# 2_unextended_ANSI_matrix.net
KiCad netlist of a schematic drawn in Altium Designer
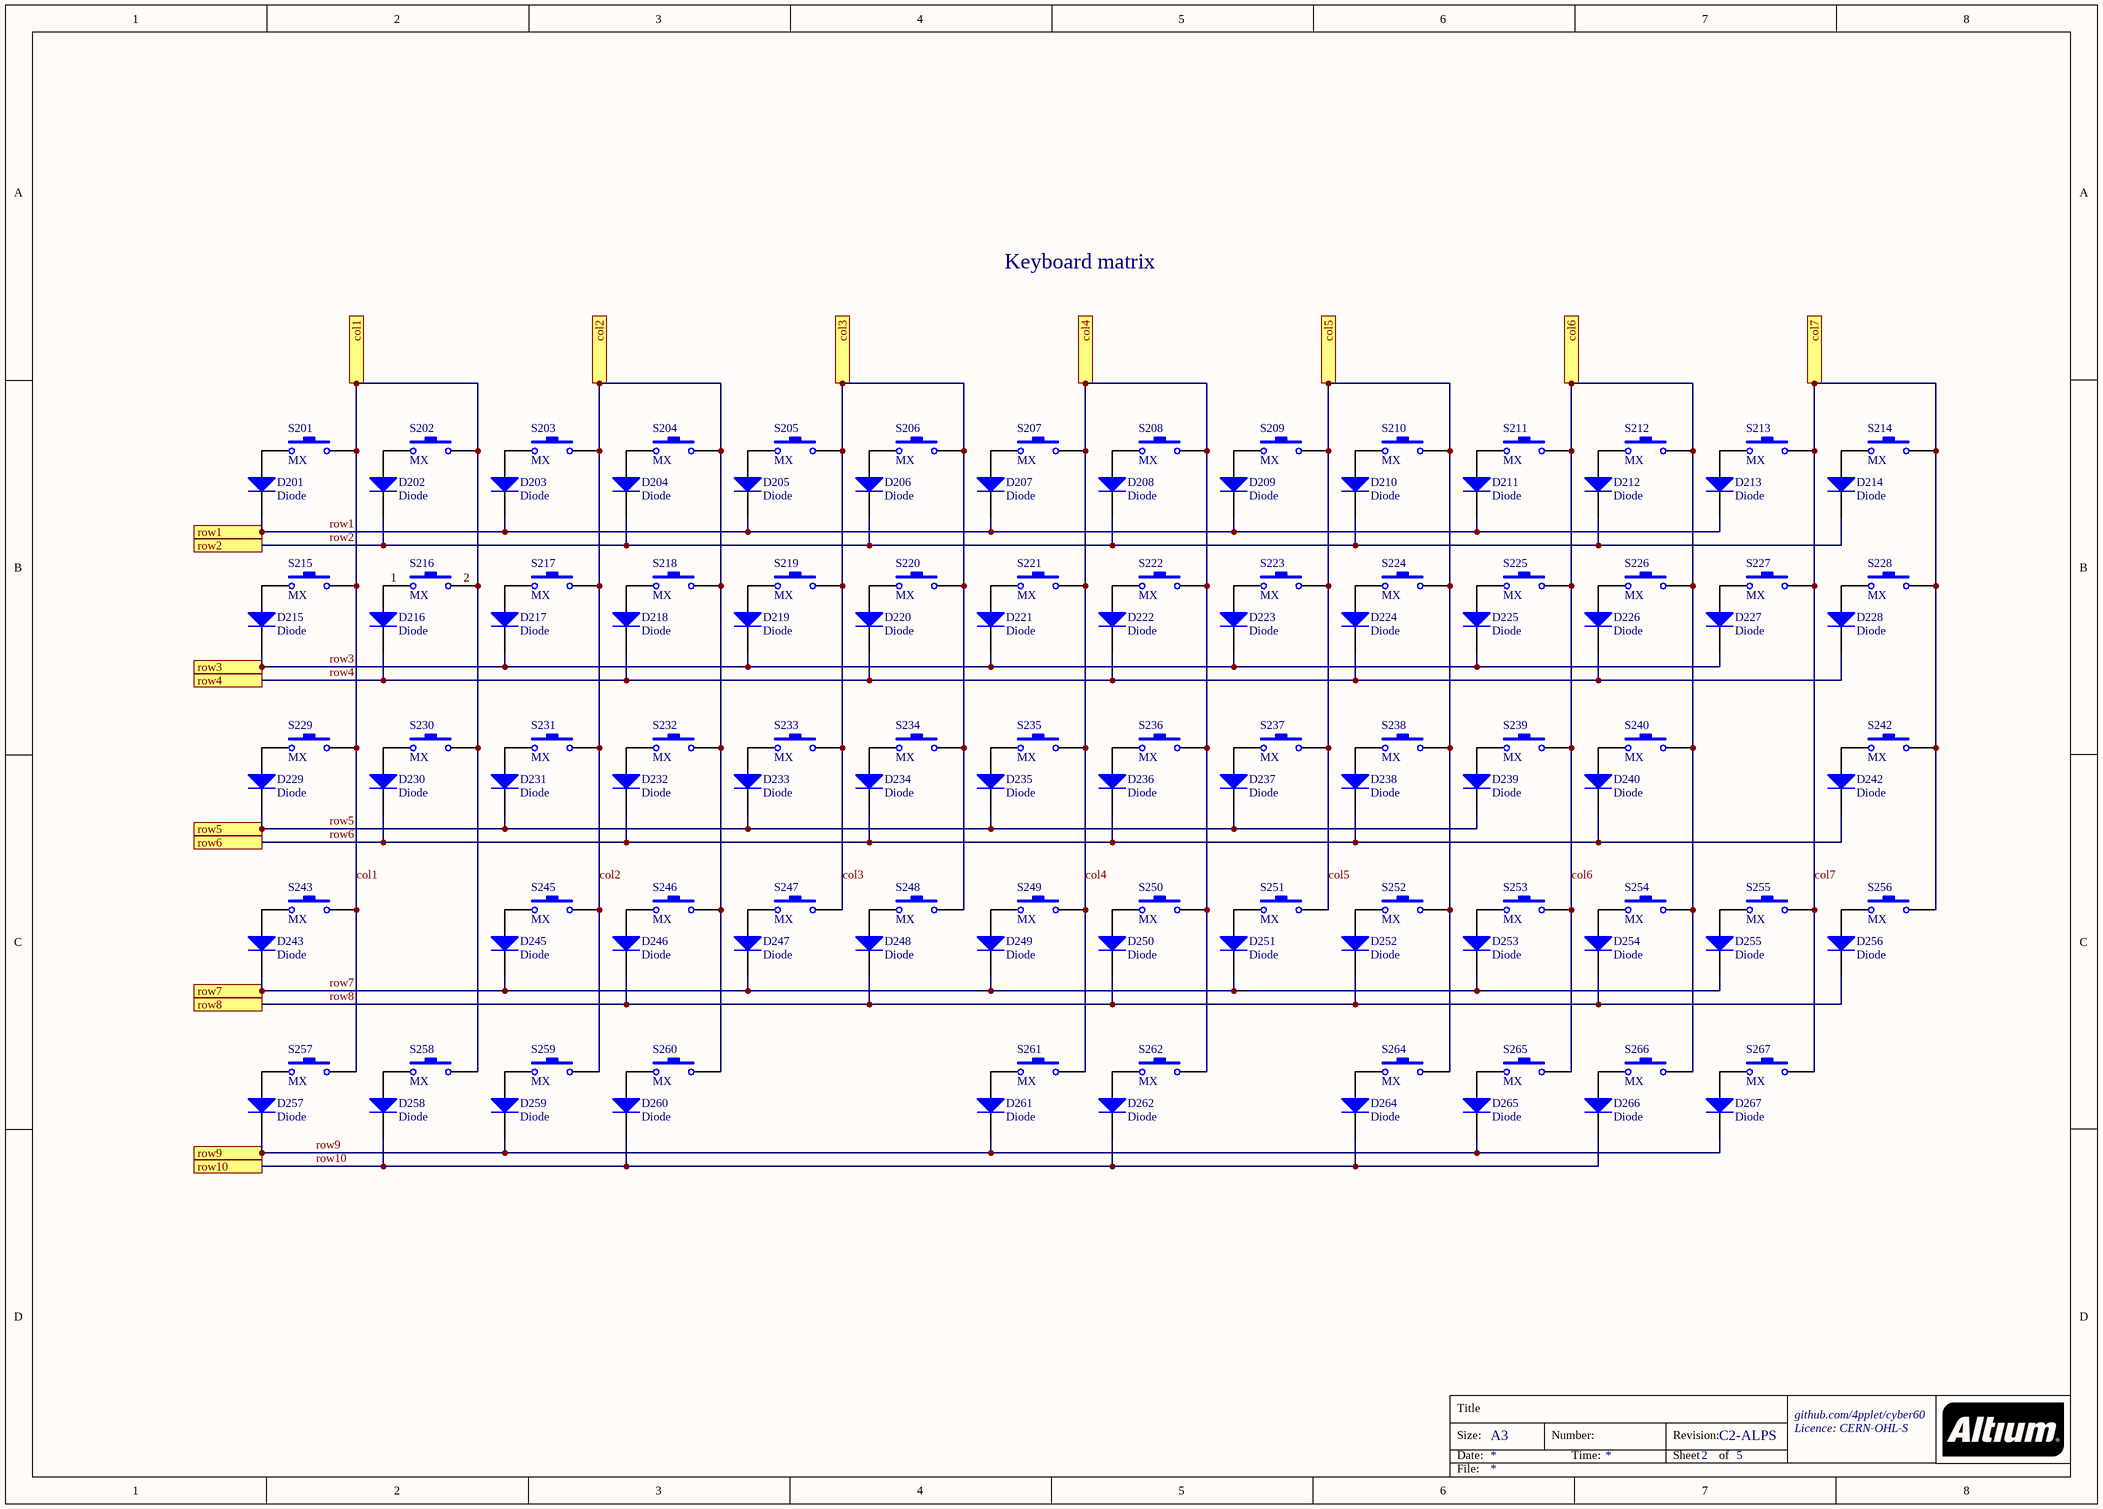
[diagram p0: 2_unextended_ANSI_matrix.SchDoc]

(export (version "E")
  (design (tool "Eeschema 10.0.6"))
  (components
    (comp (ref "D201")
      (value "Diode")
      (footprint "SOD-123")
      (description "Default Diode")
      (fields (field (name "LCSC PART #") "C81598") (field (name "MRF.PART") "1N4148W"))
      (libsource (lib "Miscellaneous Devices") (part "Diode"))
    )
    (comp (ref "D202")
      (value "Diode")
      (footprint "SOD-123")
      (description "Default Diode")
      (fields (field (name "LCSC PART #") "C81598") (field (name "MRF.PART") "1N4148W"))
      (libsource (lib "Miscellaneous Devices") (part "Diode"))
    )
    (comp (ref "D203")
      (value "Diode")
      (footprint "SOD-123")
      (description "Default Diode")
      (fields (field (name "LCSC PART #") "C81598") (field (name "MRF.PART") "1N4148W"))
      (libsource (lib "Miscellaneous Devices") (part "Diode"))
    )
    (comp (ref "D204")
      (value "Diode")
      (footprint "SOD-123")
      (description "Default Diode")
      (fields (field (name "LCSC PART #") "C81598") (field (name "MRF.PART") "1N4148W"))
      (libsource (lib "Miscellaneous Devices") (part "Diode"))
    )
    (comp (ref "D205")
      (value "Diode")
      (footprint "SOD-123")
      (description "Default Diode")
      (fields (field (name "LCSC PART #") "C81598") (field (name "MRF.PART") "1N4148W"))
      (libsource (lib "Miscellaneous Devices") (part "Diode"))
    )
    (comp (ref "D206")
      (value "Diode")
      (footprint "SOD-123")
      (description "Default Diode")
      (fields (field (name "LCSC PART #") "C81598") (field (name "MRF.PART") "1N4148W"))
      (libsource (lib "Miscellaneous Devices") (part "Diode"))
    )
    (comp (ref "D207")
      (value "Diode")
      (footprint "SOD-123")
      (description "Default Diode")
      (fields (field (name "LCSC PART #") "C81598") (field (name "MRF.PART") "1N4148W"))
      (libsource (lib "Miscellaneous Devices") (part "Diode"))
    )
    (comp (ref "D208")
      (value "Diode")
      (footprint "SOD-123")
      (description "Default Diode")
      (fields (field (name "LCSC PART #") "C81598") (field (name "MRF.PART") "1N4148W"))
      (libsource (lib "Miscellaneous Devices") (part "Diode"))
    )
    (comp (ref "D209")
      (value "Diode")
      (footprint "SOD-123")
      (description "Default Diode")
      (fields (field (name "LCSC PART #") "C81598") (field (name "MRF.PART") "1N4148W"))
      (libsource (lib "Miscellaneous Devices") (part "Diode"))
    )
    (comp (ref "D210")
      (value "Diode")
      (footprint "SOD-123")
      (description "Default Diode")
      (fields (field (name "LCSC PART #") "C81598") (field (name "MRF.PART") "1N4148W"))
      (libsource (lib "Miscellaneous Devices") (part "Diode"))
    )
    (comp (ref "D211")
      (value "Diode")
      (footprint "SOD-123")
      (description "Default Diode")
      (fields (field (name "LCSC PART #") "C81598") (field (name "MRF.PART") "1N4148W"))
      (libsource (lib "Miscellaneous Devices") (part "Diode"))
    )
    (comp (ref "D212")
      (value "Diode")
      (footprint "SOD-123")
      (description "Default Diode")
      (fields (field (name "LCSC PART #") "C81598") (field (name "MRF.PART") "1N4148W"))
      (libsource (lib "Miscellaneous Devices") (part "Diode"))
    )
    (comp (ref "D213")
      (value "Diode")
      (footprint "SOD-123")
      (description "Default Diode")
      (fields (field (name "LCSC PART #") "C81598") (field (name "MRF.PART") "1N4148W"))
      (libsource (lib "Miscellaneous Devices") (part "Diode"))
    )
    (comp (ref "D214")
      (value "Diode")
      (footprint "SOD-123")
      (description "Default Diode")
      (fields (field (name "LCSC PART #") "C81598") (field (name "MRF.PART") "1N4148W"))
      (libsource (lib "Miscellaneous Devices") (part "Diode"))
    )
    (comp (ref "D215")
      (value "Diode")
      (footprint "SOD-123")
      (description "Default Diode")
      (fields (field (name "LCSC PART #") "C81598") (field (name "MRF.PART") "1N4148W"))
      (libsource (lib "Miscellaneous Devices") (part "Diode"))
    )
    (comp (ref "D216")
      (value "Diode")
      (footprint "SOD-123")
      (description "Default Diode")
      (fields (field (name "LCSC PART #") "C81598") (field (name "MRF.PART") "1N4148W"))
      (libsource (lib "Miscellaneous Devices") (part "Diode"))
    )
    (comp (ref "D217")
      (value "Diode")
      (footprint "SOD-123")
      (description "Default Diode")
      (fields (field (name "LCSC PART #") "C81598") (field (name "MRF.PART") "1N4148W"))
      (libsource (lib "Miscellaneous Devices") (part "Diode"))
    )
    (comp (ref "D218")
      (value "Diode")
      (footprint "SOD-123")
      (description "Default Diode")
      (fields (field (name "LCSC PART #") "C81598") (field (name "MRF.PART") "1N4148W"))
      (libsource (lib "Miscellaneous Devices") (part "Diode"))
    )
    (comp (ref "D219")
      (value "Diode")
      (footprint "SOD-123")
      (description "Default Diode")
      (fields (field (name "LCSC PART #") "C81598") (field (name "MRF.PART") "1N4148W"))
      (libsource (lib "Miscellaneous Devices") (part "Diode"))
    )
    (comp (ref "D220")
      (value "Diode")
      (footprint "SOD-123")
      (description "Default Diode")
      (fields (field (name "LCSC PART #") "C81598") (field (name "MRF.PART") "1N4148W"))
      (libsource (lib "Miscellaneous Devices") (part "Diode"))
    )
    (comp (ref "D221")
      (value "Diode")
      (footprint "SOD-123")
      (description "Default Diode")
      (fields (field (name "LCSC PART #") "C81598") (field (name "MRF.PART") "1N4148W"))
      (libsource (lib "Miscellaneous Devices") (part "Diode"))
    )
    (comp (ref "D222")
      (value "Diode")
      (footprint "SOD-123")
      (description "Default Diode")
      (fields (field (name "LCSC PART #") "C81598") (field (name "MRF.PART") "1N4148W"))
      (libsource (lib "Miscellaneous Devices") (part "Diode"))
    )
    (comp (ref "D223")
      (value "Diode")
      (footprint "SOD-123")
      (description "Default Diode")
      (fields (field (name "LCSC PART #") "C81598") (field (name "MRF.PART") "1N4148W"))
      (libsource (lib "Miscellaneous Devices") (part "Diode"))
    )
    (comp (ref "D224")
      (value "Diode")
      (footprint "SOD-123")
      (description "Default Diode")
      (fields (field (name "LCSC PART #") "C81598") (field (name "MRF.PART") "1N4148W"))
      (libsource (lib "Miscellaneous Devices") (part "Diode"))
    )
    (comp (ref "D225")
      (value "Diode")
      (footprint "SOD-123")
      (description "Default Diode")
      (fields (field (name "LCSC PART #") "C81598") (field (name "MRF.PART") "1N4148W"))
      (libsource (lib "Miscellaneous Devices") (part "Diode"))
    )
    (comp (ref "D226")
      (value "Diode")
      (footprint "SOD-123")
      (description "Default Diode")
      (fields (field (name "LCSC PART #") "C81598") (field (name "MRF.PART") "1N4148W"))
      (libsource (lib "Miscellaneous Devices") (part "Diode"))
    )
    (comp (ref "D227")
      (value "Diode")
      (footprint "SOD-123")
      (description "Default Diode")
      (fields (field (name "LCSC PART #") "C81598") (field (name "MRF.PART") "1N4148W"))
      (libsource (lib "Miscellaneous Devices") (part "Diode"))
    )
    (comp (ref "D228")
      (value "Diode")
      (footprint "SOD-123")
      (description "Default Diode")
      (fields (field (name "LCSC PART #") "C81598") (field (name "MRF.PART") "1N4148W"))
      (libsource (lib "Miscellaneous Devices") (part "Diode"))
    )
    (comp (ref "D229")
      (value "Diode")
      (footprint "SOD-123")
      (description "Default Diode")
      (fields (field (name "LCSC PART #") "C81598") (field (name "MRF.PART") "1N4148W"))
      (libsource (lib "Miscellaneous Devices") (part "Diode"))
    )
    (comp (ref "D230")
      (value "Diode")
      (footprint "SOD-123")
      (description "Default Diode")
      (fields (field (name "LCSC PART #") "C81598") (field (name "MRF.PART") "1N4148W"))
      (libsource (lib "Miscellaneous Devices") (part "Diode"))
    )
    (comp (ref "D231")
      (value "Diode")
      (footprint "SOD-123")
      (description "Default Diode")
      (fields (field (name "LCSC PART #") "C81598") (field (name "MRF.PART") "1N4148W"))
      (libsource (lib "Miscellaneous Devices") (part "Diode"))
    )
    (comp (ref "D232")
      (value "Diode")
      (footprint "SOD-123")
      (description "Default Diode")
      (fields (field (name "LCSC PART #") "C81598") (field (name "MRF.PART") "1N4148W"))
      (libsource (lib "Miscellaneous Devices") (part "Diode"))
    )
    (comp (ref "D233")
      (value "Diode")
      (footprint "SOD-123")
      (description "Default Diode")
      (fields (field (name "LCSC PART #") "C81598") (field (name "MRF.PART") "1N4148W"))
      (libsource (lib "Miscellaneous Devices") (part "Diode"))
    )
    (comp (ref "D234")
      (value "Diode")
      (footprint "SOD-123")
      (description "Default Diode")
      (fields (field (name "LCSC PART #") "C81598") (field (name "MRF.PART") "1N4148W"))
      (libsource (lib "Miscellaneous Devices") (part "Diode"))
    )
    (comp (ref "D235")
      (value "Diode")
      (footprint "SOD-123")
      (description "Default Diode")
      (fields (field (name "LCSC PART #") "C81598") (field (name "MRF.PART") "1N4148W"))
      (libsource (lib "Miscellaneous Devices") (part "Diode"))
    )
    (comp (ref "D236")
      (value "Diode")
      (footprint "SOD-123")
      (description "Default Diode")
      (fields (field (name "LCSC PART #") "C81598") (field (name "MRF.PART") "1N4148W"))
      (libsource (lib "Miscellaneous Devices") (part "Diode"))
    )
    (comp (ref "D237")
      (value "Diode")
      (footprint "SOD-123")
      (description "Default Diode")
      (fields (field (name "LCSC PART #") "C81598") (field (name "MRF.PART") "1N4148W"))
      (libsource (lib "Miscellaneous Devices") (part "Diode"))
    )
    (comp (ref "D238")
      (value "Diode")
      (footprint "SOD-123")
      (description "Default Diode")
      (fields (field (name "LCSC PART #") "C81598") (field (name "MRF.PART") "1N4148W"))
      (libsource (lib "Miscellaneous Devices") (part "Diode"))
    )
    (comp (ref "D239")
      (value "Diode")
      (footprint "SOD-123")
      (description "Default Diode")
      (fields (field (name "LCSC PART #") "C81598") (field (name "MRF.PART") "1N4148W"))
      (libsource (lib "Miscellaneous Devices") (part "Diode"))
    )
    (comp (ref "D240")
      (value "Diode")
      (footprint "SOD-123")
      (description "Default Diode")
      (fields (field (name "LCSC PART #") "C81598") (field (name "MRF.PART") "1N4148W"))
      (libsource (lib "Miscellaneous Devices") (part "Diode"))
    )
    (comp (ref "D242")
      (value "Diode")
      (footprint "SOD-123")
      (description "Default Diode")
      (fields (field (name "LCSC PART #") "C81598") (field (name "MRF.PART") "1N4148W"))
      (libsource (lib "Miscellaneous Devices") (part "Diode"))
    )
    (comp (ref "D243")
      (value "Diode")
      (footprint "SOD-123")
      (description "Default Diode")
      (fields (field (name "LCSC PART #") "C81598") (field (name "MRF.PART") "1N4148W"))
      (libsource (lib "Miscellaneous Devices") (part "Diode"))
    )
    (comp (ref "D245")
      (value "Diode")
      (footprint "SOD-123")
      (description "Default Diode")
      (fields (field (name "LCSC PART #") "C81598") (field (name "MRF.PART") "1N4148W"))
      (libsource (lib "Miscellaneous Devices") (part "Diode"))
    )
    (comp (ref "D246")
      (value "Diode")
      (footprint "SOD-123")
      (description "Default Diode")
      (fields (field (name "LCSC PART #") "C81598") (field (name "MRF.PART") "1N4148W"))
      (libsource (lib "Miscellaneous Devices") (part "Diode"))
    )
    (comp (ref "D247")
      (value "Diode")
      (footprint "SOD-123")
      (description "Default Diode")
      (fields (field (name "LCSC PART #") "C81598") (field (name "MRF.PART") "1N4148W"))
      (libsource (lib "Miscellaneous Devices") (part "Diode"))
    )
    (comp (ref "D248")
      (value "Diode")
      (footprint "SOD-123")
      (description "Default Diode")
      (fields (field (name "LCSC PART #") "C81598") (field (name "MRF.PART") "1N4148W"))
      (libsource (lib "Miscellaneous Devices") (part "Diode"))
    )
    (comp (ref "D249")
      (value "Diode")
      (footprint "SOD-123")
      (description "Default Diode")
      (fields (field (name "LCSC PART #") "C81598") (field (name "MRF.PART") "1N4148W"))
      (libsource (lib "Miscellaneous Devices") (part "Diode"))
    )
    (comp (ref "D250")
      (value "Diode")
      (footprint "SOD-123")
      (description "Default Diode")
      (fields (field (name "LCSC PART #") "C81598") (field (name "MRF.PART") "1N4148W"))
      (libsource (lib "Miscellaneous Devices") (part "Diode"))
    )
    (comp (ref "D251")
      (value "Diode")
      (footprint "SOD-123")
      (description "Default Diode")
      (fields (field (name "LCSC PART #") "C81598") (field (name "MRF.PART") "1N4148W"))
      (libsource (lib "Miscellaneous Devices") (part "Diode"))
    )
    (comp (ref "D252")
      (value "Diode")
      (footprint "SOD-123")
      (description "Default Diode")
      (fields (field (name "LCSC PART #") "C81598") (field (name "MRF.PART") "1N4148W"))
      (libsource (lib "Miscellaneous Devices") (part "Diode"))
    )
    (comp (ref "D253")
      (value "Diode")
      (footprint "SOD-123")
      (description "Default Diode")
      (fields (field (name "LCSC PART #") "C81598") (field (name "MRF.PART") "1N4148W"))
      (libsource (lib "Miscellaneous Devices") (part "Diode"))
    )
    (comp (ref "D254")
      (value "Diode")
      (footprint "SOD-123")
      (description "Default Diode")
      (fields (field (name "LCSC PART #") "C81598") (field (name "MRF.PART") "1N4148W"))
      (libsource (lib "Miscellaneous Devices") (part "Diode"))
    )
    (comp (ref "D255")
      (value "Diode")
      (footprint "SOD-123")
      (description "Default Diode")
      (fields (field (name "LCSC PART #") "C81598") (field (name "MRF.PART") "1N4148W"))
      (libsource (lib "Miscellaneous Devices") (part "Diode"))
    )
    (comp (ref "D256")
      (value "Diode")
      (footprint "SOD-123")
      (description "Default Diode")
      (fields (field (name "LCSC PART #") "C81598") (field (name "MRF.PART") "1N4148W"))
      (libsource (lib "Miscellaneous Devices") (part "Diode"))
    )
    (comp (ref "D257")
      (value "Diode")
      (footprint "SOD-123")
      (description "Default Diode")
      (fields (field (name "LCSC PART #") "C81598") (field (name "MRF.PART") "1N4148W"))
      (libsource (lib "Miscellaneous Devices") (part "Diode"))
    )
    (comp (ref "D258")
      (value "Diode")
      (footprint "SOD-123")
      (description "Default Diode")
      (fields (field (name "LCSC PART #") "C81598") (field (name "MRF.PART") "1N4148W"))
      (libsource (lib "Miscellaneous Devices") (part "Diode"))
    )
    (comp (ref "D259")
      (value "Diode")
      (footprint "SOD-123")
      (description "Default Diode")
      (fields (field (name "LCSC PART #") "C81598") (field (name "MRF.PART") "1N4148W"))
      (libsource (lib "Miscellaneous Devices") (part "Diode"))
    )
    (comp (ref "D260")
      (value "Diode")
      (footprint "SOD-123")
      (description "Default Diode")
      (fields (field (name "LCSC PART #") "C81598") (field (name "MRF.PART") "1N4148W"))
      (libsource (lib "Miscellaneous Devices") (part "Diode"))
    )
    (comp (ref "D261")
      (value "Diode")
      (footprint "SOD-123")
      (description "Default Diode")
      (fields (field (name "LCSC PART #") "C81598") (field (name "MRF.PART") "1N4148W"))
      (libsource (lib "Miscellaneous Devices") (part "Diode"))
    )
    (comp (ref "D262")
      (value "Diode")
      (footprint "SOD-123")
      (description "Default Diode")
      (fields (field (name "LCSC PART #") "C81598") (field (name "MRF.PART") "1N4148W"))
      (libsource (lib "Miscellaneous Devices") (part "Diode"))
    )
    (comp (ref "D264")
      (value "Diode")
      (footprint "SOD-123")
      (description "Default Diode")
      (fields (field (name "LCSC PART #") "C81598") (field (name "MRF.PART") "1N4148W"))
      (libsource (lib "Miscellaneous Devices") (part "Diode"))
    )
    (comp (ref "D265")
      (value "Diode")
      (footprint "SOD-123")
      (description "Default Diode")
      (fields (field (name "LCSC PART #") "C81598") (field (name "MRF.PART") "1N4148W"))
      (libsource (lib "Miscellaneous Devices") (part "Diode"))
    )
    (comp (ref "D266")
      (value "Diode")
      (footprint "SOD-123")
      (description "Default Diode")
      (fields (field (name "LCSC PART #") "C81598") (field (name "MRF.PART") "1N4148W"))
      (libsource (lib "Miscellaneous Devices") (part "Diode"))
    )
    (comp (ref "D267")
      (value "Diode")
      (footprint "SOD-123")
      (description "Default Diode")
      (fields (field (name "LCSC PART #") "C81598") (field (name "MRF.PART") "1N4148W"))
      (libsource (lib "Miscellaneous Devices") (part "Diode"))
    )
    (comp (ref "S201")
      (value "MX")
      (footprint "Alps-switch - switched pol")
      (description "Switch")
      (libsource (lib "Miscellaneous Devices") (part "SW-PB"))
    )
    (comp (ref "S202")
      (value "MX")
      (footprint "Alps-switch - switched pol")
      (description "Switch")
      (libsource (lib "Miscellaneous Devices") (part "SW-PB"))
    )
    (comp (ref "S203")
      (value "MX")
      (footprint "Alps-switch - switched pol")
      (description "Switch")
      (libsource (lib "Miscellaneous Devices") (part "SW-PB"))
    )
    (comp (ref "S204")
      (value "MX")
      (footprint "Alps-switch - switched pol")
      (description "Switch")
      (libsource (lib "Miscellaneous Devices") (part "SW-PB"))
    )
    (comp (ref "S205")
      (value "MX")
      (footprint "Alps-switch - switched pol")
      (description "Switch")
      (libsource (lib "Miscellaneous Devices") (part "SW-PB"))
    )
    (comp (ref "S206")
      (value "MX")
      (footprint "Alps-switch - switched pol")
      (description "Switch")
      (libsource (lib "Miscellaneous Devices") (part "SW-PB"))
    )
    (comp (ref "S207")
      (value "MX")
      (footprint "Alps-switch - switched pol")
      (description "Switch")
      (libsource (lib "Miscellaneous Devices") (part "SW-PB"))
    )
    (comp (ref "S208")
      (value "MX")
      (footprint "Alps-switch - switched pol")
      (description "Switch")
      (libsource (lib "Miscellaneous Devices") (part "SW-PB"))
    )
    (comp (ref "S209")
      (value "MX")
      (footprint "Alps-switch - switched pol")
      (description "Switch")
      (libsource (lib "Miscellaneous Devices") (part "SW-PB"))
    )
    (comp (ref "S210")
      (value "MX")
      (footprint "Alps-switch - switched pol")
      (description "Switch")
      (libsource (lib "Miscellaneous Devices") (part "SW-PB"))
    )
    (comp (ref "S211")
      (value "MX")
      (footprint "Alps-switch - switched pol")
      (description "Switch")
      (libsource (lib "Miscellaneous Devices") (part "SW-PB"))
    )
    (comp (ref "S212")
      (value "MX")
      (footprint "Alps-switch - switched pol")
      (description "Switch")
      (libsource (lib "Miscellaneous Devices") (part "SW-PB"))
    )
    (comp (ref "S213")
      (value "MX")
      (footprint "Alps-switch - switched pol")
      (description "Switch")
      (libsource (lib "Miscellaneous Devices") (part "SW-PB"))
    )
    (comp (ref "S214")
      (value "MX")
      (footprint "Alps-switch")
      (description "Switch")
      (libsource (lib "Miscellaneous Devices") (part "SW-PB"))
    )
    (comp (ref "S215")
      (value "MX")
      (footprint "Alps-switch - switched pol")
      (description "TAB")
      (libsource (lib "Miscellaneous Devices") (part "SW-PB"))
    )
    (comp (ref "S216")
      (value "MX")
      (footprint "Alps-switch - switched pol")
      (description "Switch")
      (libsource (lib "") (part "SW-PB_1"))
    )
    (comp (ref "S217")
      (value "MX")
      (footprint "Alps-switch - switched pol")
      (description "Switch")
      (libsource (lib "Miscellaneous Devices") (part "SW-PB"))
    )
    (comp (ref "S218")
      (value "MX")
      (footprint "Alps-switch - switched pol")
      (description "Switch")
      (libsource (lib "Miscellaneous Devices") (part "SW-PB"))
    )
    (comp (ref "S219")
      (value "MX")
      (footprint "Alps-switch - switched pol")
      (description "Switch")
      (libsource (lib "Miscellaneous Devices") (part "SW-PB"))
    )
    (comp (ref "S220")
      (value "MX")
      (footprint "Alps-switch - switched pol")
      (description "Switch")
      (libsource (lib "Miscellaneous Devices") (part "SW-PB"))
    )
    (comp (ref "S221")
      (value "MX")
      (footprint "Alps-switch - switched pol")
      (description "Switch")
      (libsource (lib "Miscellaneous Devices") (part "SW-PB"))
    )
    (comp (ref "S222")
      (value "MX")
      (footprint "Alps-switch - switched pol")
      (description "Switch")
      (libsource (lib "Miscellaneous Devices") (part "SW-PB"))
    )
    (comp (ref "S223")
      (value "MX")
      (footprint "Alps-switch - switched pol")
      (description "Switch")
      (libsource (lib "Miscellaneous Devices") (part "SW-PB"))
    )
    (comp (ref "S224")
      (value "MX")
      (footprint "Alps-switch - switched pol")
      (description "Switch")
      (libsource (lib "Miscellaneous Devices") (part "SW-PB"))
    )
    (comp (ref "S225")
      (value "MX")
      (footprint "Alps-switch - switched pol")
      (description "Switch")
      (libsource (lib "Miscellaneous Devices") (part "SW-PB"))
    )
    (comp (ref "S226")
      (value "MX")
      (footprint "Alps-switch")
      (description "Switch")
      (libsource (lib "Miscellaneous Devices") (part "SW-PB"))
    )
    (comp (ref "S227")
      (value "MX")
      (footprint "Alps-switch")
      (description "Switch")
      (libsource (lib "Miscellaneous Devices") (part "SW-PB"))
    )
    (comp (ref "S228")
      (value "MX")
      (footprint "ALPS-switch - backspace no stabs")
      (description "Switch")
      (libsource (lib "Miscellaneous Devices") (part "SW-PB"))
    )
    (comp (ref "S229")
      (value "MX")
      (footprint "Alps-switch")
      (description "Switch")
      (libsource (lib "Miscellaneous Devices") (part "SW-PB"))
    )
    (comp (ref "S230")
      (value "MX")
      (footprint "Alps-switch - switched pol")
      (description "Switch")
      (libsource (lib "Miscellaneous Devices") (part "SW-PB"))
    )
    (comp (ref "S231")
      (value "MX")
      (footprint "Alps-switch - switched pol")
      (description "Switch")
      (libsource (lib "Miscellaneous Devices") (part "SW-PB"))
    )
    (comp (ref "S232")
      (value "MX")
      (footprint "Alps-switch - switched pol")
      (description "Switch")
      (libsource (lib "Miscellaneous Devices") (part "SW-PB"))
    )
    (comp (ref "S233")
      (value "MX")
      (footprint "Alps-switch - switched pol")
      (description "Switch")
      (libsource (lib "Miscellaneous Devices") (part "SW-PB"))
    )
    (comp (ref "S234")
      (value "MX")
      (footprint "Alps-switch - switched pol")
      (description "Switch")
      (libsource (lib "Miscellaneous Devices") (part "SW-PB"))
    )
    (comp (ref "S235")
      (value "MX")
      (footprint "Alps-switch - switched pol")
      (description "Switch")
      (libsource (lib "Miscellaneous Devices") (part "SW-PB"))
    )
    (comp (ref "S236")
      (value "MX")
      (footprint "Alps-switch - switched pol")
      (description "Switch")
      (libsource (lib "Miscellaneous Devices") (part "SW-PB"))
    )
    (comp (ref "S237")
      (value "MX")
      (footprint "Alps-switch - switched pol")
      (description "Switch")
      (libsource (lib "Miscellaneous Devices") (part "SW-PB"))
    )
    (comp (ref "S238")
      (value "MX")
      (footprint "Alps-switch - switched pol")
      (description "Switch")
      (libsource (lib "Miscellaneous Devices") (part "SW-PB"))
    )
    (comp (ref "S239")
      (value "MX")
      (footprint "Alps-switch")
      (description "Switch")
      (libsource (lib "Miscellaneous Devices") (part "SW-PB"))
    )
    (comp (ref "S240")
      (value "MX")
      (footprint "Alps-switch - switched pol")
      (description "Switch")
      (libsource (lib "Miscellaneous Devices") (part "SW-PB"))
    )
    (comp (ref "S242")
      (value "MX")
      (footprint "ALPS-switch - 1.5U")
      (description "Switch")
      (libsource (lib "Miscellaneous Devices") (part "SW-PB"))
    )
    (comp (ref "S243")
      (value "MX")
      (footprint "Alps-switch - switched pol")
      (description "Switch")
      (libsource (lib "Miscellaneous Devices") (part "SW-PB"))
    )
    (comp (ref "S245")
      (value "MX")
      (footprint "Alps-switch - switched pol")
      (description "Switch")
      (libsource (lib "Miscellaneous Devices") (part "SW-PB"))
    )
    (comp (ref "S246")
      (value "MX")
      (footprint "Alps-switch - switched pol")
      (description "Switch")
      (libsource (lib "Miscellaneous Devices") (part "SW-PB"))
    )
    (comp (ref "S247")
      (value "MX")
      (footprint "Alps-switch - switched pol")
      (description "Switch")
      (libsource (lib "Miscellaneous Devices") (part "SW-PB"))
    )
    (comp (ref "S248")
      (value "MX")
      (footprint "Alps-switch - switched pol")
      (description "Switch")
      (libsource (lib "Miscellaneous Devices") (part "SW-PB"))
    )
    (comp (ref "S249")
      (value "MX")
      (footprint "Alps-switch - switched pol")
      (description "Switch")
      (libsource (lib "Miscellaneous Devices") (part "SW-PB"))
    )
    (comp (ref "S250")
      (value "MX")
      (footprint "Alps-switch - switched pol")
      (description "Switch")
      (libsource (lib "Miscellaneous Devices") (part "SW-PB"))
    )
    (comp (ref "S251")
      (value "MX")
      (footprint "Alps-switch - switched pol")
      (description "Switch")
      (libsource (lib "Miscellaneous Devices") (part "SW-PB"))
    )
    (comp (ref "S252")
      (value "MX")
      (footprint "Alps-switch - switched pol")
      (description "Switch")
      (libsource (lib "Miscellaneous Devices") (part "SW-PB"))
    )
    (comp (ref "S253")
      (value "MX")
      (footprint "Alps-switch - switched pol")
      (description "Switch")
      (libsource (lib "Miscellaneous Devices") (part "SW-PB"))
    )
    (comp (ref "S254")
      (value "MX")
      (footprint "Alps-switch - switched pol")
      (description "Switch")
      (libsource (lib "Miscellaneous Devices") (part "SW-PB"))
    )
    (comp (ref "S255")
      (value "MX")
      (footprint "Alps-switch")
      (description "Switch")
      (libsource (lib "Miscellaneous Devices") (part "SW-PB"))
    )
    (comp (ref "S256")
      (value "MX")
      (footprint "Alps-switch - switched pol")
      (description "Switch")
      (libsource (lib "Miscellaneous Devices") (part "SW-PB"))
    )
    (comp (ref "S257")
      (value "MX")
      (footprint "Alps-switch - switched pol")
      (description "Switch")
      (libsource (lib "Miscellaneous Devices") (part "SW-PB"))
    )
    (comp (ref "S258")
      (value "MX")
      (footprint "Alps-switch")
      (description "Switch")
      (libsource (lib "Miscellaneous Devices") (part "SW-PB"))
    )
    (comp (ref "S259")
      (value "MX")
      (footprint "Alps-switch")
      (description "Switch")
      (libsource (lib "Miscellaneous Devices") (part "SW-PB"))
    )
    (comp (ref "S260")
      (value "MX")
      (footprint "Alps-switch")
      (description "Switch")
      (libsource (lib "Miscellaneous Devices") (part "SW-PB"))
    )
    (comp (ref "S261")
      (value "MX")
      (footprint "Alps-switch")
      (description "Switch")
      (libsource (lib "Miscellaneous Devices") (part "SW-PB"))
    )
    (comp (ref "S262")
      (value "MX")
      (footprint "Alps-switch - switched pol")
      (description "Switch")
      (libsource (lib "Miscellaneous Devices") (part "SW-PB"))
    )
    (comp (ref "S264")
      (value "MX")
      (footprint "Alps-switch")
      (description "Switch")
      (libsource (lib "Miscellaneous Devices") (part "SW-PB"))
    )
    (comp (ref "S265")
      (value "MX")
      (footprint "Alps-switch")
      (description "Switch")
      (libsource (lib "Miscellaneous Devices") (part "SW-PB"))
    )
    (comp (ref "S266")
      (value "MX")
      (footprint "Alps-switch")
      (description "Switch")
      (libsource (lib "Miscellaneous Devices") (part "SW-PB"))
    )
    (comp (ref "S267")
      (value "MX")
      (footprint "ALPS-switch - right shift - no stabs")
      (description "Switch")
      (libsource (lib "Miscellaneous Devices") (part "SW-PB"))
    )
  )
  (nets
    (net (code "1") (name "/col1") (class "Default")
      (node (ref "S201") (pin "2") (pinfunction "2_2") (pintype "passive"))
      (node (ref "S202") (pin "2") (pinfunction "2_2") (pintype "passive"))
      (node (ref "S215") (pin "2") (pinfunction "2_2") (pintype "passive"))
      (node (ref "S216") (pin "2") (pinfunction "2_2") (pintype "passive"))
      (node (ref "S229") (pin "2") (pinfunction "2_2") (pintype "passive"))
      (node (ref "S230") (pin "2") (pinfunction "2_2") (pintype "passive"))
      (node (ref "S243") (pin "2") (pinfunction "2_2") (pintype "passive"))
      (node (ref "S257") (pin "2") (pinfunction "2_2") (pintype "passive"))
      (node (ref "S258") (pin "2") (pinfunction "2_2") (pintype "passive"))
    )
    (net (code "2") (name "/col2") (class "Default")
      (node (ref "S203") (pin "2") (pinfunction "2_2") (pintype "passive"))
      (node (ref "S204") (pin "2") (pinfunction "2_2") (pintype "passive"))
      (node (ref "S217") (pin "2") (pinfunction "2_2") (pintype "passive"))
      (node (ref "S218") (pin "2") (pinfunction "2_2") (pintype "passive"))
      (node (ref "S231") (pin "2") (pinfunction "2_2") (pintype "passive"))
      (node (ref "S232") (pin "2") (pinfunction "2_2") (pintype "passive"))
      (node (ref "S245") (pin "2") (pinfunction "2_2") (pintype "passive"))
      (node (ref "S246") (pin "2") (pinfunction "2_2") (pintype "passive"))
      (node (ref "S259") (pin "2") (pinfunction "2_2") (pintype "passive"))
      (node (ref "S260") (pin "2") (pinfunction "2_2") (pintype "passive"))
    )
    (net (code "3") (name "/col3") (class "Default")
      (node (ref "S205") (pin "2") (pinfunction "2_2") (pintype "passive"))
      (node (ref "S206") (pin "2") (pinfunction "2_2") (pintype "passive"))
      (node (ref "S219") (pin "2") (pinfunction "2_2") (pintype "passive"))
      (node (ref "S220") (pin "2") (pinfunction "2_2") (pintype "passive"))
      (node (ref "S233") (pin "2") (pinfunction "2_2") (pintype "passive"))
      (node (ref "S234") (pin "2") (pinfunction "2_2") (pintype "passive"))
      (node (ref "S247") (pin "2") (pinfunction "2_2") (pintype "passive"))
      (node (ref "S248") (pin "2") (pinfunction "2_2") (pintype "passive"))
    )
    (net (code "4") (name "/col4") (class "Default")
      (node (ref "S207") (pin "2") (pinfunction "2_2") (pintype "passive"))
      (node (ref "S208") (pin "2") (pinfunction "2_2") (pintype "passive"))
      (node (ref "S221") (pin "2") (pinfunction "2_2") (pintype "passive"))
      (node (ref "S222") (pin "2") (pinfunction "2_2") (pintype "passive"))
      (node (ref "S235") (pin "2") (pinfunction "2_2") (pintype "passive"))
      (node (ref "S236") (pin "2") (pinfunction "2_2") (pintype "passive"))
      (node (ref "S249") (pin "2") (pinfunction "2_2") (pintype "passive"))
      (node (ref "S250") (pin "2") (pinfunction "2_2") (pintype "passive"))
      (node (ref "S261") (pin "1") (pinfunction "1_1") (pintype "passive"))
      (node (ref "S262") (pin "2") (pinfunction "2_2") (pintype "passive"))
    )
    (net (code "5") (name "/col5") (class "Default")
      (node (ref "S209") (pin "2") (pinfunction "2_2") (pintype "passive"))
      (node (ref "S210") (pin "2") (pinfunction "2_2") (pintype "passive"))
      (node (ref "S223") (pin "2") (pinfunction "2_2") (pintype "passive"))
      (node (ref "S224") (pin "2") (pinfunction "2_2") (pintype "passive"))
      (node (ref "S237") (pin "2") (pinfunction "2_2") (pintype "passive"))
      (node (ref "S238") (pin "2") (pinfunction "2_2") (pintype "passive"))
      (node (ref "S251") (pin "2") (pinfunction "2_2") (pintype "passive"))
      (node (ref "S252") (pin "2") (pinfunction "2_2") (pintype "passive"))
      (node (ref "S264") (pin "1") (pinfunction "1_1") (pintype "passive"))
    )
    (net (code "6") (name "/col6") (class "Default")
      (node (ref "S211") (pin "2") (pinfunction "2_2") (pintype "passive"))
      (node (ref "S212") (pin "2") (pinfunction "2_2") (pintype "passive"))
      (node (ref "S225") (pin "2") (pinfunction "2_2") (pintype "passive"))
      (node (ref "S226") (pin "2") (pinfunction "2_2") (pintype "passive"))
      (node (ref "S239") (pin "2") (pinfunction "2_2") (pintype "passive"))
      (node (ref "S240") (pin "2") (pinfunction "2_2") (pintype "passive"))
      (node (ref "S253") (pin "2") (pinfunction "2_2") (pintype "passive"))
      (node (ref "S254") (pin "2") (pinfunction "2_2") (pintype "passive"))
      (node (ref "S265") (pin "2") (pinfunction "2_2") (pintype "passive"))
      (node (ref "S266") (pin "2") (pinfunction "2_2") (pintype "passive"))
    )
    (net (code "7") (name "/col7") (class "Default")
      (node (ref "S213") (pin "2") (pinfunction "2_2") (pintype "passive"))
      (node (ref "S214") (pin "2") (pinfunction "2_2") (pintype "passive"))
      (node (ref "S227") (pin "2") (pinfunction "2_2") (pintype "passive"))
      (node (ref "S228") (pin "1") (pinfunction "1_1") (pintype "passive"))
      (node (ref "S242") (pin "2") (pinfunction "2_2") (pintype "passive"))
      (node (ref "S255") (pin "2") (pinfunction "2_2") (pintype "passive"))
      (node (ref "S256") (pin "2") (pinfunction "2_2") (pintype "passive"))
      (node (ref "S267") (pin "1") (pinfunction "1_1") (pintype "passive"))
    )
    (net (code "8") (name "/row1") (class "Default")
      (node (ref "D201") (pin "2") (pinfunction "K_2") (pintype "passive"))
      (node (ref "D203") (pin "2") (pinfunction "K_2") (pintype "passive"))
      (node (ref "D205") (pin "2") (pinfunction "K_2") (pintype "passive"))
      (node (ref "D207") (pin "2") (pinfunction "K_2") (pintype "passive"))
      (node (ref "D209") (pin "2") (pinfunction "K_2") (pintype "passive"))
      (node (ref "D211") (pin "2") (pinfunction "K_2") (pintype "passive"))
      (node (ref "D213") (pin "2") (pinfunction "K_2") (pintype "passive"))
    )
    (net (code "9") (name "/row2") (class "Default")
      (node (ref "D202") (pin "2") (pinfunction "K_2") (pintype "passive"))
      (node (ref "D204") (pin "2") (pinfunction "K_2") (pintype "passive"))
      (node (ref "D206") (pin "2") (pinfunction "K_2") (pintype "passive"))
      (node (ref "D208") (pin "2") (pinfunction "K_2") (pintype "passive"))
      (node (ref "D210") (pin "2") (pinfunction "K_2") (pintype "passive"))
      (node (ref "D212") (pin "2") (pinfunction "K_2") (pintype "passive"))
      (node (ref "D214") (pin "2") (pinfunction "K_2") (pintype "passive"))
    )
    (net (code "10") (name "/row3") (class "Default")
      (node (ref "D215") (pin "2") (pinfunction "K_2") (pintype "passive"))
      (node (ref "D217") (pin "2") (pinfunction "K_2") (pintype "passive"))
      (node (ref "D219") (pin "2") (pinfunction "K_2") (pintype "passive"))
      (node (ref "D221") (pin "2") (pinfunction "K_2") (pintype "passive"))
      (node (ref "D223") (pin "2") (pinfunction "K_2") (pintype "passive"))
      (node (ref "D225") (pin "2") (pinfunction "K_2") (pintype "passive"))
      (node (ref "D227") (pin "2") (pinfunction "K_2") (pintype "passive"))
    )
    (net (code "11") (name "/row4") (class "Default")
      (node (ref "D216") (pin "2") (pinfunction "K_2") (pintype "passive"))
      (node (ref "D218") (pin "2") (pinfunction "K_2") (pintype "passive"))
      (node (ref "D220") (pin "2") (pinfunction "K_2") (pintype "passive"))
      (node (ref "D222") (pin "2") (pinfunction "K_2") (pintype "passive"))
      (node (ref "D224") (pin "2") (pinfunction "K_2") (pintype "passive"))
      (node (ref "D226") (pin "2") (pinfunction "K_2") (pintype "passive"))
      (node (ref "D228") (pin "2") (pinfunction "K_2") (pintype "passive"))
    )
    (net (code "12") (name "/row5") (class "Default")
      (node (ref "D229") (pin "2") (pinfunction "K_2") (pintype "passive"))
      (node (ref "D231") (pin "2") (pinfunction "K_2") (pintype "passive"))
      (node (ref "D233") (pin "2") (pinfunction "K_2") (pintype "passive"))
      (node (ref "D235") (pin "2") (pinfunction "K_2") (pintype "passive"))
      (node (ref "D237") (pin "2") (pinfunction "K_2") (pintype "passive"))
      (node (ref "D239") (pin "2") (pinfunction "K_2") (pintype "passive"))
    )
    (net (code "13") (name "/row6") (class "Default")
      (node (ref "D230") (pin "2") (pinfunction "K_2") (pintype "passive"))
      (node (ref "D232") (pin "2") (pinfunction "K_2") (pintype "passive"))
      (node (ref "D234") (pin "2") (pinfunction "K_2") (pintype "passive"))
      (node (ref "D236") (pin "2") (pinfunction "K_2") (pintype "passive"))
      (node (ref "D238") (pin "2") (pinfunction "K_2") (pintype "passive"))
      (node (ref "D240") (pin "2") (pinfunction "K_2") (pintype "passive"))
      (node (ref "D242") (pin "2") (pinfunction "K_2") (pintype "passive"))
    )
    (net (code "14") (name "/row7") (class "Default")
      (node (ref "D243") (pin "2") (pinfunction "K_2") (pintype "passive"))
      (node (ref "D245") (pin "2") (pinfunction "K_2") (pintype "passive"))
      (node (ref "D247") (pin "2") (pinfunction "K_2") (pintype "passive"))
      (node (ref "D249") (pin "2") (pinfunction "K_2") (pintype "passive"))
      (node (ref "D251") (pin "2") (pinfunction "K_2") (pintype "passive"))
      (node (ref "D253") (pin "2") (pinfunction "K_2") (pintype "passive"))
      (node (ref "D255") (pin "2") (pinfunction "K_2") (pintype "passive"))
    )
    (net (code "15") (name "/row8") (class "Default")
      (node (ref "D246") (pin "2") (pinfunction "K_2") (pintype "passive"))
      (node (ref "D248") (pin "2") (pinfunction "K_2") (pintype "passive"))
      (node (ref "D250") (pin "2") (pinfunction "K_2") (pintype "passive"))
      (node (ref "D252") (pin "2") (pinfunction "K_2") (pintype "passive"))
      (node (ref "D254") (pin "2") (pinfunction "K_2") (pintype "passive"))
      (node (ref "D256") (pin "2") (pinfunction "K_2") (pintype "passive"))
    )
    (net (code "16") (name "/row9") (class "Default")
      (node (ref "D257") (pin "2") (pinfunction "K_2") (pintype "passive"))
      (node (ref "D259") (pin "2") (pinfunction "K_2") (pintype "passive"))
      (node (ref "D261") (pin "2") (pinfunction "K_2") (pintype "passive"))
      (node (ref "D265") (pin "2") (pinfunction "K_2") (pintype "passive"))
      (node (ref "D267") (pin "2") (pinfunction "K_2") (pintype "passive"))
    )
    (net (code "17") (name "/row10") (class "Default")
      (node (ref "D258") (pin "2") (pinfunction "K_2") (pintype "passive"))
      (node (ref "D260") (pin "2") (pinfunction "K_2") (pintype "passive"))
      (node (ref "D262") (pin "2") (pinfunction "K_2") (pintype "passive"))
      (node (ref "D264") (pin "2") (pinfunction "K_2") (pintype "passive"))
      (node (ref "D266") (pin "2") (pinfunction "K_2") (pintype "passive"))
    )
    (net (code "18") (name "Net-(D201-A)") (class "Default")
      (node (ref "D201") (pin "1") (pinfunction "A_1") (pintype "passive"))
      (node (ref "S201") (pin "1") (pinfunction "1_1") (pintype "passive"))
    )
    (net (code "19") (name "Net-(D202-A)") (class "Default")
      (node (ref "D202") (pin "1") (pinfunction "A_1") (pintype "passive"))
      (node (ref "S202") (pin "1") (pinfunction "1_1") (pintype "passive"))
    )
    (net (code "20") (name "Net-(D203-A)") (class "Default")
      (node (ref "D203") (pin "1") (pinfunction "A_1") (pintype "passive"))
      (node (ref "S203") (pin "1") (pinfunction "1_1") (pintype "passive"))
    )
    (net (code "21") (name "Net-(D204-A)") (class "Default")
      (node (ref "D204") (pin "1") (pinfunction "A_1") (pintype "passive"))
      (node (ref "S204") (pin "1") (pinfunction "1_1") (pintype "passive"))
    )
    (net (code "22") (name "Net-(D205-A)") (class "Default")
      (node (ref "D205") (pin "1") (pinfunction "A_1") (pintype "passive"))
      (node (ref "S205") (pin "1") (pinfunction "1_1") (pintype "passive"))
    )
    (net (code "23") (name "Net-(D206-A)") (class "Default")
      (node (ref "D206") (pin "1") (pinfunction "A_1") (pintype "passive"))
      (node (ref "S206") (pin "1") (pinfunction "1_1") (pintype "passive"))
    )
    (net (code "24") (name "Net-(D207-A)") (class "Default")
      (node (ref "D207") (pin "1") (pinfunction "A_1") (pintype "passive"))
      (node (ref "S207") (pin "1") (pinfunction "1_1") (pintype "passive"))
    )
    (net (code "25") (name "Net-(D208-A)") (class "Default")
      (node (ref "D208") (pin "1") (pinfunction "A_1") (pintype "passive"))
      (node (ref "S208") (pin "1") (pinfunction "1_1") (pintype "passive"))
    )
    (net (code "26") (name "Net-(D209-A)") (class "Default")
      (node (ref "D209") (pin "1") (pinfunction "A_1") (pintype "passive"))
      (node (ref "S209") (pin "1") (pinfunction "1_1") (pintype "passive"))
    )
    (net (code "27") (name "Net-(D210-A)") (class "Default")
      (node (ref "D210") (pin "1") (pinfunction "A_1") (pintype "passive"))
      (node (ref "S210") (pin "1") (pinfunction "1_1") (pintype "passive"))
    )
    (net (code "28") (name "Net-(D211-A)") (class "Default")
      (node (ref "D211") (pin "1") (pinfunction "A_1") (pintype "passive"))
      (node (ref "S211") (pin "1") (pinfunction "1_1") (pintype "passive"))
    )
    (net (code "29") (name "Net-(D212-A)") (class "Default")
      (node (ref "D212") (pin "1") (pinfunction "A_1") (pintype "passive"))
      (node (ref "S212") (pin "1") (pinfunction "1_1") (pintype "passive"))
    )
    (net (code "30") (name "Net-(D213-A)") (class "Default")
      (node (ref "D213") (pin "1") (pinfunction "A_1") (pintype "passive"))
      (node (ref "S213") (pin "1") (pinfunction "1_1") (pintype "passive"))
    )
    (net (code "31") (name "Net-(D214-A)") (class "Default")
      (node (ref "D214") (pin "1") (pinfunction "A_1") (pintype "passive"))
      (node (ref "S214") (pin "1") (pinfunction "1_1") (pintype "passive"))
    )
    (net (code "32") (name "Net-(D215-A)") (class "Default")
      (node (ref "D215") (pin "1") (pinfunction "A_1") (pintype "passive"))
      (node (ref "S215") (pin "1") (pinfunction "1_1") (pintype "passive"))
    )
    (net (code "33") (name "Net-(D216-A)") (class "Default")
      (node (ref "D216") (pin "1") (pinfunction "A_1") (pintype "passive"))
      (node (ref "S216") (pin "1") (pinfunction "1_1") (pintype "passive"))
    )
    (net (code "34") (name "Net-(D217-A)") (class "Default")
      (node (ref "D217") (pin "1") (pinfunction "A_1") (pintype "passive"))
      (node (ref "S217") (pin "1") (pinfunction "1_1") (pintype "passive"))
    )
    (net (code "35") (name "Net-(D218-A)") (class "Default")
      (node (ref "D218") (pin "1") (pinfunction "A_1") (pintype "passive"))
      (node (ref "S218") (pin "1") (pinfunction "1_1") (pintype "passive"))
    )
    (net (code "36") (name "Net-(D219-A)") (class "Default")
      (node (ref "D219") (pin "1") (pinfunction "A_1") (pintype "passive"))
      (node (ref "S219") (pin "1") (pinfunction "1_1") (pintype "passive"))
    )
    (net (code "37") (name "Net-(D220-A)") (class "Default")
      (node (ref "D220") (pin "1") (pinfunction "A_1") (pintype "passive"))
      (node (ref "S220") (pin "1") (pinfunction "1_1") (pintype "passive"))
    )
    (net (code "38") (name "Net-(D221-A)") (class "Default")
      (node (ref "D221") (pin "1") (pinfunction "A_1") (pintype "passive"))
      (node (ref "S221") (pin "1") (pinfunction "1_1") (pintype "passive"))
    )
    (net (code "39") (name "Net-(D222-A)") (class "Default")
      (node (ref "D222") (pin "1") (pinfunction "A_1") (pintype "passive"))
      (node (ref "S222") (pin "1") (pinfunction "1_1") (pintype "passive"))
    )
    (net (code "40") (name "Net-(D223-A)") (class "Default")
      (node (ref "D223") (pin "1") (pinfunction "A_1") (pintype "passive"))
      (node (ref "S223") (pin "1") (pinfunction "1_1") (pintype "passive"))
    )
    (net (code "41") (name "Net-(D224-A)") (class "Default")
      (node (ref "D224") (pin "1") (pinfunction "A_1") (pintype "passive"))
      (node (ref "S224") (pin "1") (pinfunction "1_1") (pintype "passive"))
    )
    (net (code "42") (name "Net-(D225-A)") (class "Default")
      (node (ref "D225") (pin "1") (pinfunction "A_1") (pintype "passive"))
      (node (ref "S225") (pin "1") (pinfunction "1_1") (pintype "passive"))
    )
    (net (code "43") (name "Net-(D226-A)") (class "Default")
      (node (ref "D226") (pin "1") (pinfunction "A_1") (pintype "passive"))
      (node (ref "S226") (pin "1") (pinfunction "1_1") (pintype "passive"))
    )
    (net (code "44") (name "Net-(D227-A)") (class "Default")
      (node (ref "D227") (pin "1") (pinfunction "A_1") (pintype "passive"))
      (node (ref "S227") (pin "1") (pinfunction "1_1") (pintype "passive"))
    )
    (net (code "45") (name "Net-(D228-A)") (class "Default")
      (node (ref "D228") (pin "1") (pinfunction "A_1") (pintype "passive"))
      (node (ref "S228") (pin "2") (pinfunction "2_2") (pintype "passive"))
    )
    (net (code "46") (name "Net-(D229-A)") (class "Default")
      (node (ref "D229") (pin "1") (pinfunction "A_1") (pintype "passive"))
      (node (ref "S229") (pin "1") (pinfunction "1_1") (pintype "passive"))
    )
    (net (code "47") (name "Net-(D230-A)") (class "Default")
      (node (ref "D230") (pin "1") (pinfunction "A_1") (pintype "passive"))
      (node (ref "S230") (pin "1") (pinfunction "1_1") (pintype "passive"))
    )
    (net (code "48") (name "Net-(D231-A)") (class "Default")
      (node (ref "D231") (pin "1") (pinfunction "A_1") (pintype "passive"))
      (node (ref "S231") (pin "1") (pinfunction "1_1") (pintype "passive"))
    )
    (net (code "49") (name "Net-(D232-A)") (class "Default")
      (node (ref "D232") (pin "1") (pinfunction "A_1") (pintype "passive"))
      (node (ref "S232") (pin "1") (pinfunction "1_1") (pintype "passive"))
    )
    (net (code "50") (name "Net-(D233-A)") (class "Default")
      (node (ref "D233") (pin "1") (pinfunction "A_1") (pintype "passive"))
      (node (ref "S233") (pin "1") (pinfunction "1_1") (pintype "passive"))
    )
    (net (code "51") (name "Net-(D234-A)") (class "Default")
      (node (ref "D234") (pin "1") (pinfunction "A_1") (pintype "passive"))
      (node (ref "S234") (pin "1") (pinfunction "1_1") (pintype "passive"))
    )
    (net (code "52") (name "Net-(D235-A)") (class "Default")
      (node (ref "D235") (pin "1") (pinfunction "A_1") (pintype "passive"))
      (node (ref "S235") (pin "1") (pinfunction "1_1") (pintype "passive"))
    )
    (net (code "53") (name "Net-(D236-A)") (class "Default")
      (node (ref "D236") (pin "1") (pinfunction "A_1") (pintype "passive"))
      (node (ref "S236") (pin "1") (pinfunction "1_1") (pintype "passive"))
    )
    (net (code "54") (name "Net-(D237-A)") (class "Default")
      (node (ref "D237") (pin "1") (pinfunction "A_1") (pintype "passive"))
      (node (ref "S237") (pin "1") (pinfunction "1_1") (pintype "passive"))
    )
    (net (code "55") (name "Net-(D238-A)") (class "Default")
      (node (ref "D238") (pin "1") (pinfunction "A_1") (pintype "passive"))
      (node (ref "S238") (pin "1") (pinfunction "1_1") (pintype "passive"))
    )
    (net (code "56") (name "Net-(D239-A)") (class "Default")
      (node (ref "D239") (pin "1") (pinfunction "A_1") (pintype "passive"))
      (node (ref "S239") (pin "1") (pinfunction "1_1") (pintype "passive"))
    )
    (net (code "57") (name "Net-(D240-A)") (class "Default")
      (node (ref "D240") (pin "1") (pinfunction "A_1") (pintype "passive"))
      (node (ref "S240") (pin "1") (pinfunction "1_1") (pintype "passive"))
    )
    (net (code "58") (name "Net-(D242-A)") (class "Default")
      (node (ref "D242") (pin "1") (pinfunction "A_1") (pintype "passive"))
      (node (ref "S242") (pin "1") (pinfunction "1_1") (pintype "passive"))
    )
    (net (code "59") (name "Net-(D243-A)") (class "Default")
      (node (ref "D243") (pin "1") (pinfunction "A_1") (pintype "passive"))
      (node (ref "S243") (pin "1") (pinfunction "1_1") (pintype "passive"))
    )
    (net (code "60") (name "Net-(D245-A)") (class "Default")
      (node (ref "D245") (pin "1") (pinfunction "A_1") (pintype "passive"))
      (node (ref "S245") (pin "1") (pinfunction "1_1") (pintype "passive"))
    )
    (net (code "61") (name "Net-(D246-A)") (class "Default")
      (node (ref "D246") (pin "1") (pinfunction "A_1") (pintype "passive"))
      (node (ref "S246") (pin "1") (pinfunction "1_1") (pintype "passive"))
    )
    (net (code "62") (name "Net-(D247-A)") (class "Default")
      (node (ref "D247") (pin "1") (pinfunction "A_1") (pintype "passive"))
      (node (ref "S247") (pin "1") (pinfunction "1_1") (pintype "passive"))
    )
    (net (code "63") (name "Net-(D248-A)") (class "Default")
      (node (ref "D248") (pin "1") (pinfunction "A_1") (pintype "passive"))
      (node (ref "S248") (pin "1") (pinfunction "1_1") (pintype "passive"))
    )
    (net (code "64") (name "Net-(D249-A)") (class "Default")
      (node (ref "D249") (pin "1") (pinfunction "A_1") (pintype "passive"))
      (node (ref "S249") (pin "1") (pinfunction "1_1") (pintype "passive"))
    )
    (net (code "65") (name "Net-(D250-A)") (class "Default")
      (node (ref "D250") (pin "1") (pinfunction "A_1") (pintype "passive"))
      (node (ref "S250") (pin "1") (pinfunction "1_1") (pintype "passive"))
    )
    (net (code "66") (name "Net-(D251-A)") (class "Default")
      (node (ref "D251") (pin "1") (pinfunction "A_1") (pintype "passive"))
      (node (ref "S251") (pin "1") (pinfunction "1_1") (pintype "passive"))
    )
    (net (code "67") (name "Net-(D252-A)") (class "Default")
      (node (ref "D252") (pin "1") (pinfunction "A_1") (pintype "passive"))
      (node (ref "S252") (pin "1") (pinfunction "1_1") (pintype "passive"))
    )
    (net (code "68") (name "Net-(D253-A)") (class "Default")
      (node (ref "D253") (pin "1") (pinfunction "A_1") (pintype "passive"))
      (node (ref "S253") (pin "1") (pinfunction "1_1") (pintype "passive"))
    )
    (net (code "69") (name "Net-(D254-A)") (class "Default")
      (node (ref "D254") (pin "1") (pinfunction "A_1") (pintype "passive"))
      (node (ref "S254") (pin "1") (pinfunction "1_1") (pintype "passive"))
    )
    (net (code "70") (name "Net-(D255-A)") (class "Default")
      (node (ref "D255") (pin "1") (pinfunction "A_1") (pintype "passive"))
      (node (ref "S255") (pin "1") (pinfunction "1_1") (pintype "passive"))
    )
    (net (code "71") (name "Net-(D256-A)") (class "Default")
      (node (ref "D256") (pin "1") (pinfunction "A_1") (pintype "passive"))
      (node (ref "S256") (pin "1") (pinfunction "1_1") (pintype "passive"))
    )
    (net (code "72") (name "Net-(D257-A)") (class "Default")
      (node (ref "D257") (pin "1") (pinfunction "A_1") (pintype "passive"))
      (node (ref "S257") (pin "1") (pinfunction "1_1") (pintype "passive"))
    )
    (net (code "73") (name "Net-(D258-A)") (class "Default")
      (node (ref "D258") (pin "1") (pinfunction "A_1") (pintype "passive"))
      (node (ref "S258") (pin "1") (pinfunction "1_1") (pintype "passive"))
    )
    (net (code "74") (name "Net-(D259-A)") (class "Default")
      (node (ref "D259") (pin "1") (pinfunction "A_1") (pintype "passive"))
      (node (ref "S259") (pin "1") (pinfunction "1_1") (pintype "passive"))
    )
    (net (code "75") (name "Net-(D260-A)") (class "Default")
      (node (ref "D260") (pin "1") (pinfunction "A_1") (pintype "passive"))
      (node (ref "S260") (pin "1") (pinfunction "1_1") (pintype "passive"))
    )
    (net (code "76") (name "Net-(D261-A)") (class "Default")
      (node (ref "D261") (pin "1") (pinfunction "A_1") (pintype "passive"))
      (node (ref "S261") (pin "2") (pinfunction "2_2") (pintype "passive"))
    )
    (net (code "77") (name "Net-(D262-A)") (class "Default")
      (node (ref "D262") (pin "1") (pinfunction "A_1") (pintype "passive"))
      (node (ref "S262") (pin "1") (pinfunction "1_1") (pintype "passive"))
    )
    (net (code "78") (name "Net-(D264-A)") (class "Default")
      (node (ref "D264") (pin "1") (pinfunction "A_1") (pintype "passive"))
      (node (ref "S264") (pin "2") (pinfunction "2_2") (pintype "passive"))
    )
    (net (code "79") (name "Net-(D265-A)") (class "Default")
      (node (ref "D265") (pin "1") (pinfunction "A_1") (pintype "passive"))
      (node (ref "S265") (pin "1") (pinfunction "1_1") (pintype "passive"))
    )
    (net (code "80") (name "Net-(D266-A)") (class "Default")
      (node (ref "D266") (pin "1") (pinfunction "A_1") (pintype "passive"))
      (node (ref "S266") (pin "1") (pinfunction "1_1") (pintype "passive"))
    )
    (net (code "81") (name "Net-(D267-A)") (class "Default")
      (node (ref "D267") (pin "1") (pinfunction "A_1") (pintype "passive"))
      (node (ref "S267") (pin "2") (pinfunction "2_2") (pintype "passive"))
    )
  )
)
